# 02_4G.net
KiCad netlist of a schematic drawn in Altium Designer
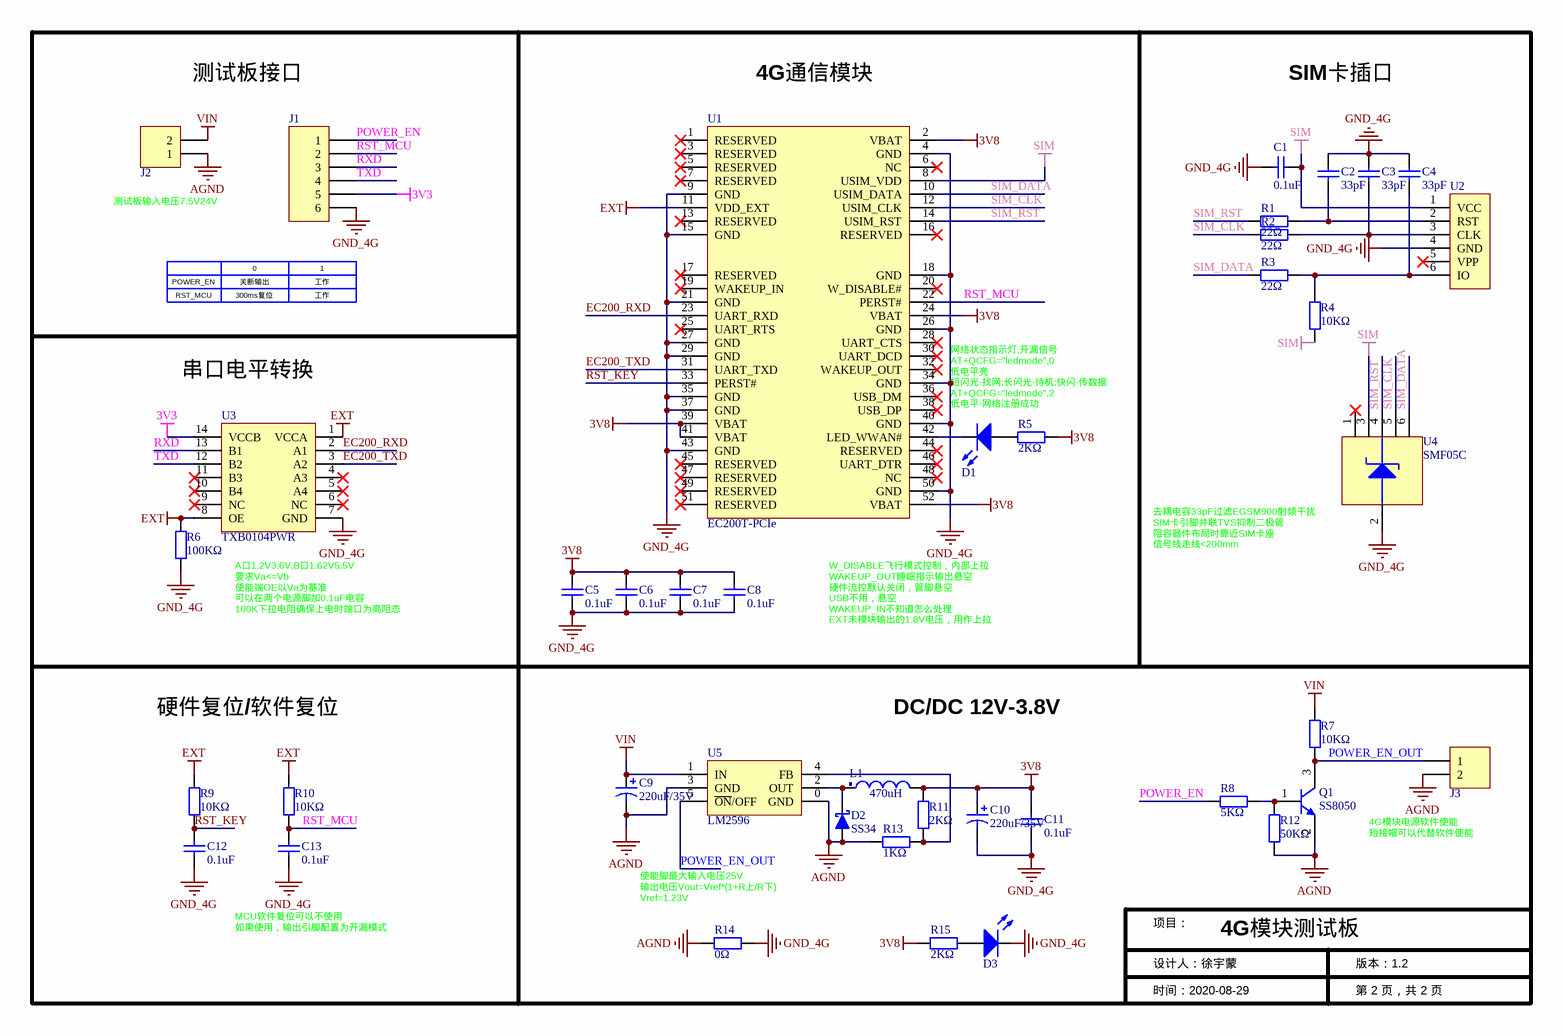
[diagram p0: 02_4G模块测试板原理图.SchDoc]

(export (version "E")
  (design (tool "Eeschema 10.0.6"))
  (components
    (comp (ref "C1")
      (value "0.1uF")
      (footprint "CAP-0603")
      (description "无极性电容")
      (fields (field (name "Comment") "Cap") (field (name "PUBLISHER") "Altium Limited"))
      (libsource (lib "Arrowy_Racing") (part "Cap"))
    )
    (comp (ref "C2")
      (value "33pF")
      (footprint "CAP-0603")
      (description "无极性电容")
      (fields (field (name "Comment") "Cap") (field (name "PUBLISHER") "Altium Limited"))
      (libsource (lib "Arrowy_Racing") (part "Cap"))
    )
    (comp (ref "C3")
      (value "33pF")
      (footprint "CAP-0603")
      (description "无极性电容")
      (fields (field (name "Comment") "Cap") (field (name "PUBLISHER") "Altium Limited"))
      (libsource (lib "Arrowy_Racing") (part "Cap"))
    )
    (comp (ref "C4")
      (value "33pF")
      (footprint "CAP-0603")
      (description "无极性电容")
      (fields (field (name "Comment") "Cap") (field (name "PUBLISHER") "Altium Limited"))
      (libsource (lib "Arrowy_Racing") (part "Cap"))
    )
    (comp (ref "C5")
      (value "0.1uF")
      (footprint "CAP-0603")
      (description "无极性电容")
      (fields (field (name "Comment") "Cap") (field (name "PUBLISHER") "Altium Limited"))
      (libsource (lib "Arrowy_Racing") (part "Cap"))
    )
    (comp (ref "C6")
      (value "0.1uF")
      (footprint "CAP-0603")
      (description "无极性电容")
      (fields (field (name "Comment") "Cap") (field (name "PUBLISHER") "Altium Limited"))
      (libsource (lib "Arrowy_Racing") (part "Cap"))
    )
    (comp (ref "C7")
      (value "0.1uF")
      (footprint "CAP-0603")
      (description "无极性电容")
      (fields (field (name "Comment") "Cap") (field (name "PUBLISHER") "Altium Limited"))
      (libsource (lib "Arrowy_Racing") (part "Cap"))
    )
    (comp (ref "C8")
      (value "0.1uF")
      (footprint "CAP-0603")
      (description "无极性电容")
      (fields (field (name "Comment") "Cap") (field (name "PUBLISHER") "Altium Limited"))
      (libsource (lib "Arrowy_Racing") (part "Cap"))
    )
    (comp (ref "C9")
      (value "220uF/35V")
      (footprint "Cap8x10.5mm")
      (description "贴片电解电容 8*10.5mm")
      (fields (field (name "Comment") "Cap Pol") (field (name "PUBLISHER") "Altium Limited"))
      (libsource (lib "元件库") (part "Cap Pol"))
    )
    (comp (ref "C10")
      (value "220uF/35V")
      (footprint "Cap8x10.5mm")
      (description "贴片电解电容 8*10.5mm")
      (fields (field (name "Comment") "Cap Pol") (field (name "PUBLISHER") "Altium Limited"))
      (libsource (lib "元件库") (part "Cap Pol"))
    )
    (comp (ref "C11")
      (value "0.1uF")
      (footprint "CAP-0603")
      (description "无极性电容")
      (fields (field (name "Comment") "Cap") (field (name "PUBLISHER") "Altium Limited"))
      (libsource (lib "Arrowy_Racing") (part "Cap"))
    )
    (comp (ref "C12")
      (value "0.1uF")
      (footprint "CAP-0603")
      (description "无极性电容")
      (fields (field (name "Comment") "Cap") (field (name "PUBLISHER") "Altium Limited"))
      (libsource (lib "Arrowy_Racing") (part "Cap"))
    )
    (comp (ref "C13")
      (value "0.1uF")
      (footprint "CAP-0603")
      (description "无极性电容")
      (fields (field (name "Comment") "Cap") (field (name "PUBLISHER") "Altium Limited"))
      (libsource (lib "Arrowy_Racing") (part "Cap"))
    )
    (comp (ref "D1")
      (value "LED")
      (footprint "LED_0805")
      (description "发光二极管")
      (fields (field (name "PUBLISHER") "Altium Limited"))
      (libsource (lib "Arrowy_Racing") (part "LED"))
    )
    (comp (ref "D2")
      (value "SS34")
      (footprint "SMA(DO-214AC)")
      (description "Schottky Diode")
      (fields (field (name "PUBLISHER") "Altium Limited"))
      (libsource (lib "元件库") (part "D Schottky"))
    )
    (comp (ref "D3")
      (value "LED")
      (footprint "LED_0805")
      (description "发光二极管")
      (fields (field (name "PUBLISHER") "Altium Limited"))
      (libsource (lib "Arrowy_Racing") (part "LED"))
    )
    (comp (ref "J1")
      (value "Header6")
      (footprint "Header_6x1_2.54_排针")
      (description "接插件")
      (libsource (lib "Arrowy_Racing") (part "Header6"))
    )
    (comp (ref "J2")
      (value "Header 2")
      (footprint "Header_HT_2P_5.08_Right")
      (description "接插件")
      (fields (field (name "PUBLISHER") "Altium Limited"))
      (libsource (lib "Arrowy_Racing") (part "Header 2"))
    )
    (comp (ref "J3")
      (value "Header 2")
      (footprint "Header_2X1_2.54")
      (description "接插件")
      (fields (field (name "PUBLISHER") "Altium Limited"))
      (libsource (lib "") (part "Header 2_1"))
    )
    (comp (ref "L1")
      (value "470uH")
      (footprint "CD43")
      (description "贴片功率电感")
      (fields (field (name "Comment") "Inductor") (field (name "PUBLISHER") "Altium Limited"))
      (libsource (lib "元件库") (part "Inductor"))
    )
    (comp (ref "Q1")
      (value "SS8050")
      (footprint "SOT-23")
      (description "NPN贴片三极管")
      (fields (field (name "PUBLISHER") "Altium Limited"))
      (libsource (lib "Arrowy_Racing") (part "SS8050"))
    )
    (comp (ref "R1")
      (value "22Ω")
      (footprint "0603")
      (description "贴片电阻")
      (fields (field (name "Comment") "Res") (field (name "PUBLISHER") "Altium Limited"))
      (libsource (lib "") (part "Res_1"))
    )
    (comp (ref "R2")
      (value "22Ω")
      (footprint "0603")
      (description "贴片电阻")
      (fields (field (name "Comment") "Res") (field (name "PUBLISHER") "Altium Limited"))
      (libsource (lib "") (part "Res_1"))
    )
    (comp (ref "R3")
      (value "22Ω")
      (footprint "0603")
      (description "贴片电阻")
      (fields (field (name "Comment") "Res") (field (name "PUBLISHER") "Altium Limited"))
      (libsource (lib "") (part "Res_1"))
    )
    (comp (ref "R4")
      (value "10KΩ")
      (footprint "0603")
      (description "贴片电阻")
      (fields (field (name "Comment") "Res") (field (name "PUBLISHER") "Altium Limited"))
      (libsource (lib "Arrowy_Racing") (part "Res"))
    )
    (comp (ref "R5")
      (value "2KΩ")
      (footprint "0603")
      (description "贴片电阻")
      (fields (field (name "Comment") "Res") (field (name "PUBLISHER") "Altium Limited"))
      (libsource (lib "") (part "Res_2"))
    )
    (comp (ref "R6")
      (value "100KΩ")
      (footprint "0603")
      (description "贴片电阻")
      (fields (field (name "Comment") "Res") (field (name "PUBLISHER") "Altium Limited"))
      (libsource (lib "") (part "Res_1"))
    )
    (comp (ref "R7")
      (value "10KΩ")
      (footprint "0603")
      (description "贴片电阻")
      (fields (field (name "Comment") "Res") (field (name "PUBLISHER") "Altium Limited"))
      (libsource (lib "Arrowy_Racing") (part "Res"))
    )
    (comp (ref "R8")
      (value "5KΩ")
      (footprint "0603")
      (description "贴片电阻")
      (fields (field (name "Comment") "Res") (field (name "PUBLISHER") "Altium Limited"))
      (libsource (lib "") (part "Res_1"))
    )
    (comp (ref "R9")
      (value "10KΩ")
      (footprint "0603")
      (description "贴片电阻")
      (fields (field (name "Comment") "Res") (field (name "PUBLISHER") "Altium Limited"))
      (libsource (lib "") (part "Res_3"))
    )
    (comp (ref "R10")
      (value "10KΩ")
      (footprint "0603")
      (description "贴片电阻")
      (fields (field (name "Comment") "Res") (field (name "PUBLISHER") "Altium Limited"))
      (libsource (lib "Arrowy_Racing") (part "Res"))
    )
    (comp (ref "R11")
      (value "2KΩ")
      (footprint "0603")
      (description "贴片电阻")
      (fields (field (name "Comment") "Res") (field (name "PUBLISHER") "Altium Limited"))
      (libsource (lib "Arrowy_Racing") (part "Res"))
    )
    (comp (ref "R12")
      (value "50KΩ")
      (footprint "0603")
      (description "贴片电阻")
      (fields (field (name "Comment") "Res") (field (name "PUBLISHER") "Altium Limited"))
      (libsource (lib "Arrowy_Racing") (part "Res"))
    )
    (comp (ref "R13")
      (value "1KΩ")
      (footprint "0603")
      (description "贴片电阻")
      (fields (field (name "Comment") "Res") (field (name "PUBLISHER") "Altium Limited"))
      (libsource (lib "") (part "Res_1"))
    )
    (comp (ref "R14")
      (value "0Ω")
      (footprint "0805")
      (description "贴片电阻")
      (fields (field (name "Comment") "Res") (field (name "PUBLISHER") "Altium Limited"))
      (libsource (lib "") (part "Res_1"))
    )
    (comp (ref "R15")
      (value "2KΩ")
      (footprint "0603")
      (description "贴片电阻")
      (fields (field (name "Comment") "Res") (field (name "PUBLISHER") "Altium Limited"))
      (libsource (lib "") (part "Res_2"))
    )
    (comp (ref "U1")
      (value "EC200T-PCIe")
      (footprint "miniPCIe1")
      (libsource (lib "Arrowy_Racing") (part "EC200T-PCIe"))
    )
    (comp (ref "U2")
      (value "nano_sim")
      (footprint "Nano_SIM_6P")
      (libsource (lib "Arrowy_Racing") (part "nano_sim"))
    )
    (comp (ref "U3")
      (value "TXB0104PWR")
      (footprint "TSSOP-14")
      (description "电平转换芯片")
      (libsource (lib "Arrowy_Racing") (part "TXB0104PWR"))
    )
    (comp (ref "U4") (value "SMF05C") (footprint "SOT-363") (libsource (lib "Arrowy_Racing") (part "SMF05C")))
    (comp (ref "U5")
      (value "LM2596")
      (footprint "TO-263-5 无背面散热")
      (description "DC/DC")
      (libsource (lib "Arrowy_Racing") (part "LM2596"))
    )
  )
  (nets
    (net (code "1") (name "/EC200_RXD") (class "Default")
      (node (ref "U1") (pin "23") (pinfunction "UART_RXD_23") (pintype "passive"))
      (node (ref "U3") (pin "2") (pinfunction "A1_2") (pintype "passive"))
    )
    (net (code "2") (name "/EC200_TXD") (class "Default")
      (node (ref "U1") (pin "31") (pinfunction "UART_TXD_31") (pintype "passive"))
      (node (ref "U3") (pin "3") (pinfunction "A2_3") (pintype "passive"))
    )
    (net (code "3") (name "/POWER_EN") (class "Default")
      (node (ref "J1") (pin "1") (pinfunction "1_1") (pintype "passive"))
      (node (ref "R8") (pin "1") (pinfunction "1_1") (pintype "passive"))
    )
    (net (code "4") (name "/POWER_EN_OUT") (class "Default")
      (node (ref "J3") (pin "1") (pinfunction "1_1") (pintype "passive"))
      (node (ref "Q1") (pin "3") (pinfunction "C_3") (pintype "passive"))
      (node (ref "R7") (pin "2") (pinfunction "2_2") (pintype "passive"))
      (node (ref "U5") (pin "5") (pinfunction "~{ON}/OFF_5") (pintype "passive"))
    )
    (net (code "5") (name "/RST_KEY") (class "Default")
      (node (ref "C12") (pin "2") (pinfunction "2_2") (pintype "passive"))
      (node (ref "R9") (pin "1") (pinfunction "1_1") (pintype "passive"))
      (node (ref "U1") (pin "33") (pinfunction "PERST#_33") (pintype "passive"))
    )
    (net (code "6") (name "/RST_MCU") (class "Default")
      (node (ref "C13") (pin "1") (pinfunction "1_1") (pintype "passive"))
      (node (ref "J1") (pin "2") (pinfunction "2_2") (pintype "passive"))
      (node (ref "R10") (pin "2") (pinfunction "2_2") (pintype "passive"))
      (node (ref "U1") (pin "22") (pinfunction "PERST#_22") (pintype "passive"))
    )
    (net (code "7") (name "/RXD") (class "Default")
      (node (ref "J1") (pin "3") (pinfunction "3_3") (pintype "passive"))
      (node (ref "U3") (pin "13") (pinfunction "B1_13") (pintype "passive"))
    )
    (net (code "8") (name "/SIM_CLK") (class "Default")
      (node (ref "R2") (pin "1") (pinfunction "1_1") (pintype "passive"))
      (node (ref "U1") (pin "12") (pinfunction "USIM_CLK_12") (pintype "passive"))
      (node (ref "U4") (pin "5") (pinfunction "gnd_5") (pintype "passive"))
    )
    (net (code "9") (name "/SIM_DATA") (class "Default")
      (node (ref "R3") (pin "1") (pinfunction "1_1") (pintype "passive"))
      (node (ref "U1") (pin "10") (pinfunction "USIM_DATA_10") (pintype "passive"))
      (node (ref "U4") (pin "6") (pinfunction "gnd_6") (pintype "passive"))
    )
    (net (code "10") (name "/SIM_RST") (class "Default")
      (node (ref "R1") (pin "1") (pinfunction "1_1") (pintype "passive"))
      (node (ref "U1") (pin "14") (pinfunction "USIM_RST_14") (pintype "passive"))
      (node (ref "U4") (pin "4") (pinfunction "gnd_4") (pintype "passive"))
    )
    (net (code "11") (name "/TXD") (class "Default")
      (node (ref "J1") (pin "4") (pinfunction "4_4") (pintype "passive"))
      (node (ref "U3") (pin "12") (pinfunction "B2_12") (pintype "passive"))
    )
    (net (code "12") (name "3V3") (class "Default")
      (node (ref "J1") (pin "5") (pinfunction "5_5") (pintype "passive"))
      (node (ref "U3") (pin "14") (pinfunction "VCCB_14") (pintype "passive"))
    )
    (net (code "13") (name "3V8") (class "Default")
      (node (ref "C10") (pin "1") (pinfunction "1_1") (pintype "passive"))
      (node (ref "C11") (pin "2") (pinfunction "2_2") (pintype "passive"))
      (node (ref "C5") (pin "2") (pinfunction "2_2") (pintype "passive"))
      (node (ref "C6") (pin "2") (pinfunction "2_2") (pintype "passive"))
      (node (ref "C7") (pin "2") (pinfunction "2_2") (pintype "passive"))
      (node (ref "C8") (pin "2") (pinfunction "2_2") (pintype "passive"))
      (node (ref "L1") (pin "2") (pinfunction "2_2") (pintype "passive"))
      (node (ref "R11") (pin "1") (pinfunction "1_1") (pintype "passive"))
      (node (ref "R15") (pin "2") (pinfunction "2_2") (pintype "passive"))
      (node (ref "R5") (pin "1") (pinfunction "1_1") (pintype "passive"))
      (node (ref "U1") (pin "2") (pinfunction "VBAT_2") (pintype "passive"))
      (node (ref "U1") (pin "24") (pinfunction "VBAT_24") (pintype "passive"))
      (node (ref "U1") (pin "39") (pinfunction "VBAT_39") (pintype "passive"))
      (node (ref "U1") (pin "41") (pinfunction "VBAT_41") (pintype "passive"))
      (node (ref "U1") (pin "52") (pinfunction "VBAT_52") (pintype "passive"))
    )
    (net (code "14") (name "AGND") (class "Default")
      (node (ref "C9") (pin "2") (pinfunction "2_2") (pintype "passive"))
      (node (ref "D2") (pin "1") (pinfunction "A_1") (pintype "passive"))
      (node (ref "J2") (pin "1") (pinfunction "1_1") (pintype "passive"))
      (node (ref "J3") (pin "2") (pinfunction "2_2") (pintype "passive"))
      (node (ref "Q1") (pin "2") (pinfunction "E_2") (pintype "passive"))
      (node (ref "R12") (pin "2") (pinfunction "2_2") (pintype "passive"))
      (node (ref "R13") (pin "1") (pinfunction "1_1") (pintype "passive"))
      (node (ref "R14") (pin "1") (pinfunction "1_1") (pintype "passive"))
      (node (ref "U5") (pin "0") (pinfunction "GND_0") (pintype "passive"))
      (node (ref "U5") (pin "3") (pinfunction "GND_3") (pintype "passive"))
    )
    (net (code "15") (name "EXT") (class "Default")
      (node (ref "R10") (pin "1") (pinfunction "1_1") (pintype "passive"))
      (node (ref "R6") (pin "2") (pinfunction "2_2") (pintype "passive"))
      (node (ref "R9") (pin "2") (pinfunction "2_2") (pintype "passive"))
      (node (ref "U1") (pin "11") (pinfunction "VDD_EXT_11") (pintype "passive"))
      (node (ref "U3") (pin "1") (pinfunction "VCCA_1") (pintype "passive"))
      (node (ref "U3") (pin "8") (pinfunction "OE_8") (pintype "passive"))
    )
    (net (code "16") (name "GND_4G") (class "Default")
      (node (ref "C1") (pin "2") (pinfunction "2_2") (pintype "passive"))
      (node (ref "C10") (pin "2") (pinfunction "2_2") (pintype "passive"))
      (node (ref "C11") (pin "1") (pinfunction "1_1") (pintype "passive"))
      (node (ref "C12") (pin "1") (pinfunction "1_1") (pintype "passive"))
      (node (ref "C13") (pin "2") (pinfunction "2_2") (pintype "passive"))
      (node (ref "C2") (pin "1") (pinfunction "1_1") (pintype "passive"))
      (node (ref "C3") (pin "1") (pinfunction "1_1") (pintype "passive"))
      (node (ref "C4") (pin "2") (pinfunction "2_2") (pintype "passive"))
      (node (ref "C5") (pin "1") (pinfunction "1_1") (pintype "passive"))
      (node (ref "C6") (pin "1") (pinfunction "1_1") (pintype "passive"))
      (node (ref "C7") (pin "1") (pinfunction "1_1") (pintype "passive"))
      (node (ref "C8") (pin "1") (pinfunction "1_1") (pintype "passive"))
      (node (ref "D3") (pin "2") (pinfunction "K_2") (pintype "passive"))
      (node (ref "J1") (pin "6") (pinfunction "6_6") (pintype "passive"))
      (node (ref "R14") (pin "2") (pinfunction "2_2") (pintype "passive"))
      (node (ref "R6") (pin "1") (pinfunction "1_1") (pintype "passive"))
      (node (ref "U1") (pin "15") (pinfunction "GND_15") (pintype "passive"))
      (node (ref "U1") (pin "18") (pinfunction "GND_18") (pintype "passive"))
      (node (ref "U1") (pin "21") (pinfunction "GND_21") (pintype "passive"))
      (node (ref "U1") (pin "26") (pinfunction "GND_26") (pintype "passive"))
      (node (ref "U1") (pin "27") (pinfunction "GND_27") (pintype "passive"))
      (node (ref "U1") (pin "29") (pinfunction "GND_29") (pintype "passive"))
      (node (ref "U1") (pin "34") (pinfunction "GND_34") (pintype "passive"))
      (node (ref "U1") (pin "35") (pinfunction "GND_35") (pintype "passive"))
      (node (ref "U1") (pin "37") (pinfunction "GND_37") (pintype "passive"))
      (node (ref "U1") (pin "4") (pinfunction "GND_4") (pintype "passive"))
      (node (ref "U1") (pin "40") (pinfunction "GND_40") (pintype "passive"))
      (node (ref "U1") (pin "43") (pinfunction "GND_43") (pintype "passive"))
      (node (ref "U1") (pin "50") (pinfunction "GND_50") (pintype "passive"))
      (node (ref "U1") (pin "9") (pinfunction "GND_9") (pintype "passive"))
      (node (ref "U2") (pin "4") (pinfunction "GND_4") (pintype "passive"))
      (node (ref "U3") (pin "7") (pinfunction "GND_7") (pintype "passive"))
      (node (ref "U4") (pin "2") (pinfunction "gnd_2") (pintype "passive"))
    )
    (net (code "17") (name "Net-(D1-A)") (class "Default")
      (node (ref "D1") (pin "1") (pinfunction "A_1") (pintype "passive"))
      (node (ref "R5") (pin "2") (pinfunction "2_2") (pintype "passive"))
    )
    (net (code "18") (name "Net-(D1-K)") (class "Default")
      (node (ref "D1") (pin "2") (pinfunction "K_2") (pintype "passive"))
      (node (ref "U1") (pin "42") (pinfunction "LED_WWAN#_42") (pintype "passive"))
    )
    (net (code "19") (name "Net-(D2-K)") (class "Default")
      (node (ref "D2") (pin "2") (pinfunction "K_2") (pintype "passive"))
      (node (ref "L1") (pin "1") (pinfunction "1_1") (pintype "passive"))
      (node (ref "U5") (pin "2") (pinfunction "OUT_2") (pintype "passive"))
    )
    (net (code "20") (name "Net-(D3-A)") (class "Default")
      (node (ref "D3") (pin "1") (pinfunction "A_1") (pintype "passive"))
      (node (ref "R15") (pin "1") (pinfunction "1_1") (pintype "passive"))
    )
    (net (code "21") (name "Net-(Q1-B)") (class "Default")
      (node (ref "Q1") (pin "1") (pinfunction "B_1") (pintype "passive"))
      (node (ref "R12") (pin "1") (pinfunction "1_1") (pintype "passive"))
      (node (ref "R8") (pin "2") (pinfunction "2_2") (pintype "passive"))
    )
    (net (code "22") (name "Net-(U2-CLK)") (class "Default")
      (node (ref "C3") (pin "2") (pinfunction "2_2") (pintype "passive"))
      (node (ref "R2") (pin "2") (pinfunction "2_2") (pintype "passive"))
      (node (ref "U2") (pin "3") (pinfunction "CLK_3") (pintype "passive"))
    )
    (net (code "23") (name "Net-(U2-IO)") (class "Default")
      (node (ref "C4") (pin "1") (pinfunction "1_1") (pintype "passive"))
      (node (ref "R3") (pin "2") (pinfunction "2_2") (pintype "passive"))
      (node (ref "R4") (pin "1") (pinfunction "1_1") (pintype "passive"))
      (node (ref "U2") (pin "6") (pinfunction "IO_6") (pintype "passive"))
    )
    (net (code "24") (name "Net-(U2-RST)") (class "Default")
      (node (ref "C2") (pin "2") (pinfunction "2_2") (pintype "passive"))
      (node (ref "R1") (pin "2") (pinfunction "2_2") (pintype "passive"))
      (node (ref "U2") (pin "2") (pinfunction "RST_2") (pintype "passive"))
    )
    (net (code "25") (name "Net-(U5-FB)") (class "Default")
      (node (ref "R11") (pin "2") (pinfunction "2_2") (pintype "passive"))
      (node (ref "R13") (pin "2") (pinfunction "2_2") (pintype "passive"))
      (node (ref "U5") (pin "4") (pinfunction "FB_4") (pintype "passive"))
    )
    (net (code "26") (name "SIM") (class "Default")
      (node (ref "C1") (pin "1") (pinfunction "1_1") (pintype "passive"))
      (node (ref "R4") (pin "2") (pinfunction "2_2") (pintype "passive"))
      (node (ref "U1") (pin "8") (pinfunction "USIM_VDD_8") (pintype "passive"))
      (node (ref "U2") (pin "1") (pinfunction "VCC_1") (pintype "passive"))
      (node (ref "U4") (pin "3") (pinfunction "gnd_3") (pintype "passive"))
    )
    (net (code "27") (name "VIN") (class "Default")
      (node (ref "C9") (pin "1") (pinfunction "1_1") (pintype "passive"))
      (node (ref "J2") (pin "2") (pinfunction "2_2") (pintype "passive"))
      (node (ref "R7") (pin "1") (pinfunction "1_1") (pintype "passive"))
      (node (ref "U5") (pin "1") (pinfunction "IN_1") (pintype "passive"))
    )
    (net (code "28") (name "unconnected-(U1-NC-Pad6)") (class "Default")
      (node (ref "U1") (pin "6") (pinfunction "NC_6") (pintype "passive+no_connect"))
    )
    (net (code "29") (name "unconnected-(U1-NC-Pad48)") (class "Default")
      (node (ref "U1") (pin "48") (pinfunction "NC_48") (pintype "passive+no_connect"))
    )
    (net (code "30") (name "unconnected-(U1-RESERVED-Pad1)") (class "Default")
      (node (ref "U1") (pin "1") (pinfunction "RESERVED_1") (pintype "passive+no_connect"))
    )
    (net (code "31") (name "unconnected-(U1-RESERVED-Pad3)") (class "Default")
      (node (ref "U1") (pin "3") (pinfunction "RESERVED_3") (pintype "passive+no_connect"))
    )
    (net (code "32") (name "unconnected-(U1-RESERVED-Pad5)") (class "Default")
      (node (ref "U1") (pin "5") (pinfunction "RESERVED_5") (pintype "passive+no_connect"))
    )
    (net (code "33") (name "unconnected-(U1-RESERVED-Pad7)") (class "Default")
      (node (ref "U1") (pin "7") (pinfunction "RESERVED_7") (pintype "passive+no_connect"))
    )
    (net (code "34") (name "unconnected-(U1-RESERVED-Pad13)") (class "Default")
      (node (ref "U1") (pin "13") (pinfunction "RESERVED_13") (pintype "passive+no_connect"))
    )
    (net (code "35") (name "unconnected-(U1-RESERVED-Pad16)") (class "Default")
      (node (ref "U1") (pin "16") (pinfunction "RESERVED_16") (pintype "passive+no_connect"))
    )
    (net (code "36") (name "unconnected-(U1-RESERVED-Pad17)") (class "Default")
      (node (ref "U1") (pin "17") (pinfunction "RESERVED_17") (pintype "passive+no_connect"))
    )
    (net (code "37") (name "unconnected-(U1-RESERVED-Pad44)") (class "Default")
      (node (ref "U1") (pin "44") (pinfunction "RESERVED_44") (pintype "passive+no_connect"))
    )
    (net (code "38") (name "unconnected-(U1-RESERVED-Pad45)") (class "Default")
      (node (ref "U1") (pin "45") (pinfunction "RESERVED_45") (pintype "passive+no_connect"))
    )
    (net (code "39") (name "unconnected-(U1-RESERVED-Pad47)") (class "Default")
      (node (ref "U1") (pin "47") (pinfunction "RESERVED_47") (pintype "passive+no_connect"))
    )
    (net (code "40") (name "unconnected-(U1-RESERVED-Pad49)") (class "Default")
      (node (ref "U1") (pin "49") (pinfunction "RESERVED_49") (pintype "passive+no_connect"))
    )
    (net (code "41") (name "unconnected-(U1-RESERVED-Pad51)") (class "Default")
      (node (ref "U1") (pin "51") (pinfunction "RESERVED_51") (pintype "passive+no_connect"))
    )
    (net (code "42") (name "unconnected-(U1-UART_CTS-Pad28)") (class "Default")
      (node (ref "U1") (pin "28") (pinfunction "UART_CTS_28") (pintype "passive+no_connect"))
    )
    (net (code "43") (name "unconnected-(U1-UART_DCD-Pad30)") (class "Default")
      (node (ref "U1") (pin "30") (pinfunction "UART_DCD_30") (pintype "passive+no_connect"))
    )
    (net (code "44") (name "unconnected-(U1-UART_DTR-Pad46)") (class "Default")
      (node (ref "U1") (pin "46") (pinfunction "UART_DTR_46") (pintype "passive+no_connect"))
    )
    (net (code "45") (name "unconnected-(U1-UART_RTS-Pad25)") (class "Default")
      (node (ref "U1") (pin "25") (pinfunction "UART_RTS_25") (pintype "passive+no_connect"))
    )
    (net (code "46") (name "unconnected-(U1-USB_DM-Pad36)") (class "Default")
      (node (ref "U1") (pin "36") (pinfunction "USB_DM_36") (pintype "passive+no_connect"))
    )
    (net (code "47") (name "unconnected-(U1-USB_DP-Pad38)") (class "Default")
      (node (ref "U1") (pin "38") (pinfunction "USB_DP_38") (pintype "passive+no_connect"))
    )
    (net (code "48") (name "unconnected-(U1-WAKEUP_IN-Pad19)") (class "Default")
      (node (ref "U1") (pin "19") (pinfunction "WAKEUP_IN_19") (pintype "passive+no_connect"))
    )
    (net (code "49") (name "unconnected-(U1-WAKEUP_OUT-Pad32)") (class "Default")
      (node (ref "U1") (pin "32") (pinfunction "WAKEUP_OUT_32") (pintype "passive+no_connect"))
    )
    (net (code "50") (name "unconnected-(U1-W_DISABLE#-Pad20)") (class "Default")
      (node (ref "U1") (pin "20") (pinfunction "W_DISABLE#_20") (pintype "passive+no_connect"))
    )
    (net (code "51") (name "unconnected-(U2-VPP-Pad5)") (class "Default")
      (node (ref "U2") (pin "5") (pinfunction "VPP_5") (pintype "passive+no_connect"))
    )
    (net (code "52") (name "unconnected-(U3-A3-Pad4)") (class "Default")
      (node (ref "U3") (pin "4") (pinfunction "A3_4") (pintype "passive+no_connect"))
    )
    (net (code "53") (name "unconnected-(U3-A4-Pad5)") (class "Default")
      (node (ref "U3") (pin "5") (pinfunction "A4_5") (pintype "passive+no_connect"))
    )
    (net (code "54") (name "unconnected-(U3-B3-Pad11)") (class "Default")
      (node (ref "U3") (pin "11") (pinfunction "B3_11") (pintype "passive+no_connect"))
    )
    (net (code "55") (name "unconnected-(U3-B4-Pad10)") (class "Default")
      (node (ref "U3") (pin "10") (pinfunction "B4_10") (pintype "passive+no_connect"))
    )
    (net (code "56") (name "unconnected-(U3-NC-Pad6)") (class "Default")
      (node (ref "U3") (pin "6") (pinfunction "NC_6") (pintype "passive+no_connect"))
    )
    (net (code "57") (name "unconnected-(U3-NC-Pad9)") (class "Default")
      (node (ref "U3") (pin "9") (pinfunction "NC_9") (pintype "passive+no_connect"))
    )
    (net (code "58") (name "unconnected-(U4-gnd-Pad1)") (class "Default")
      (node (ref "U4") (pin "1") (pinfunction "gnd_1") (pintype "passive+no_connect"))
    )
  )
)
